# ESP32_UWB.net
KiCad netlist of a schematic drawn in EAGLE
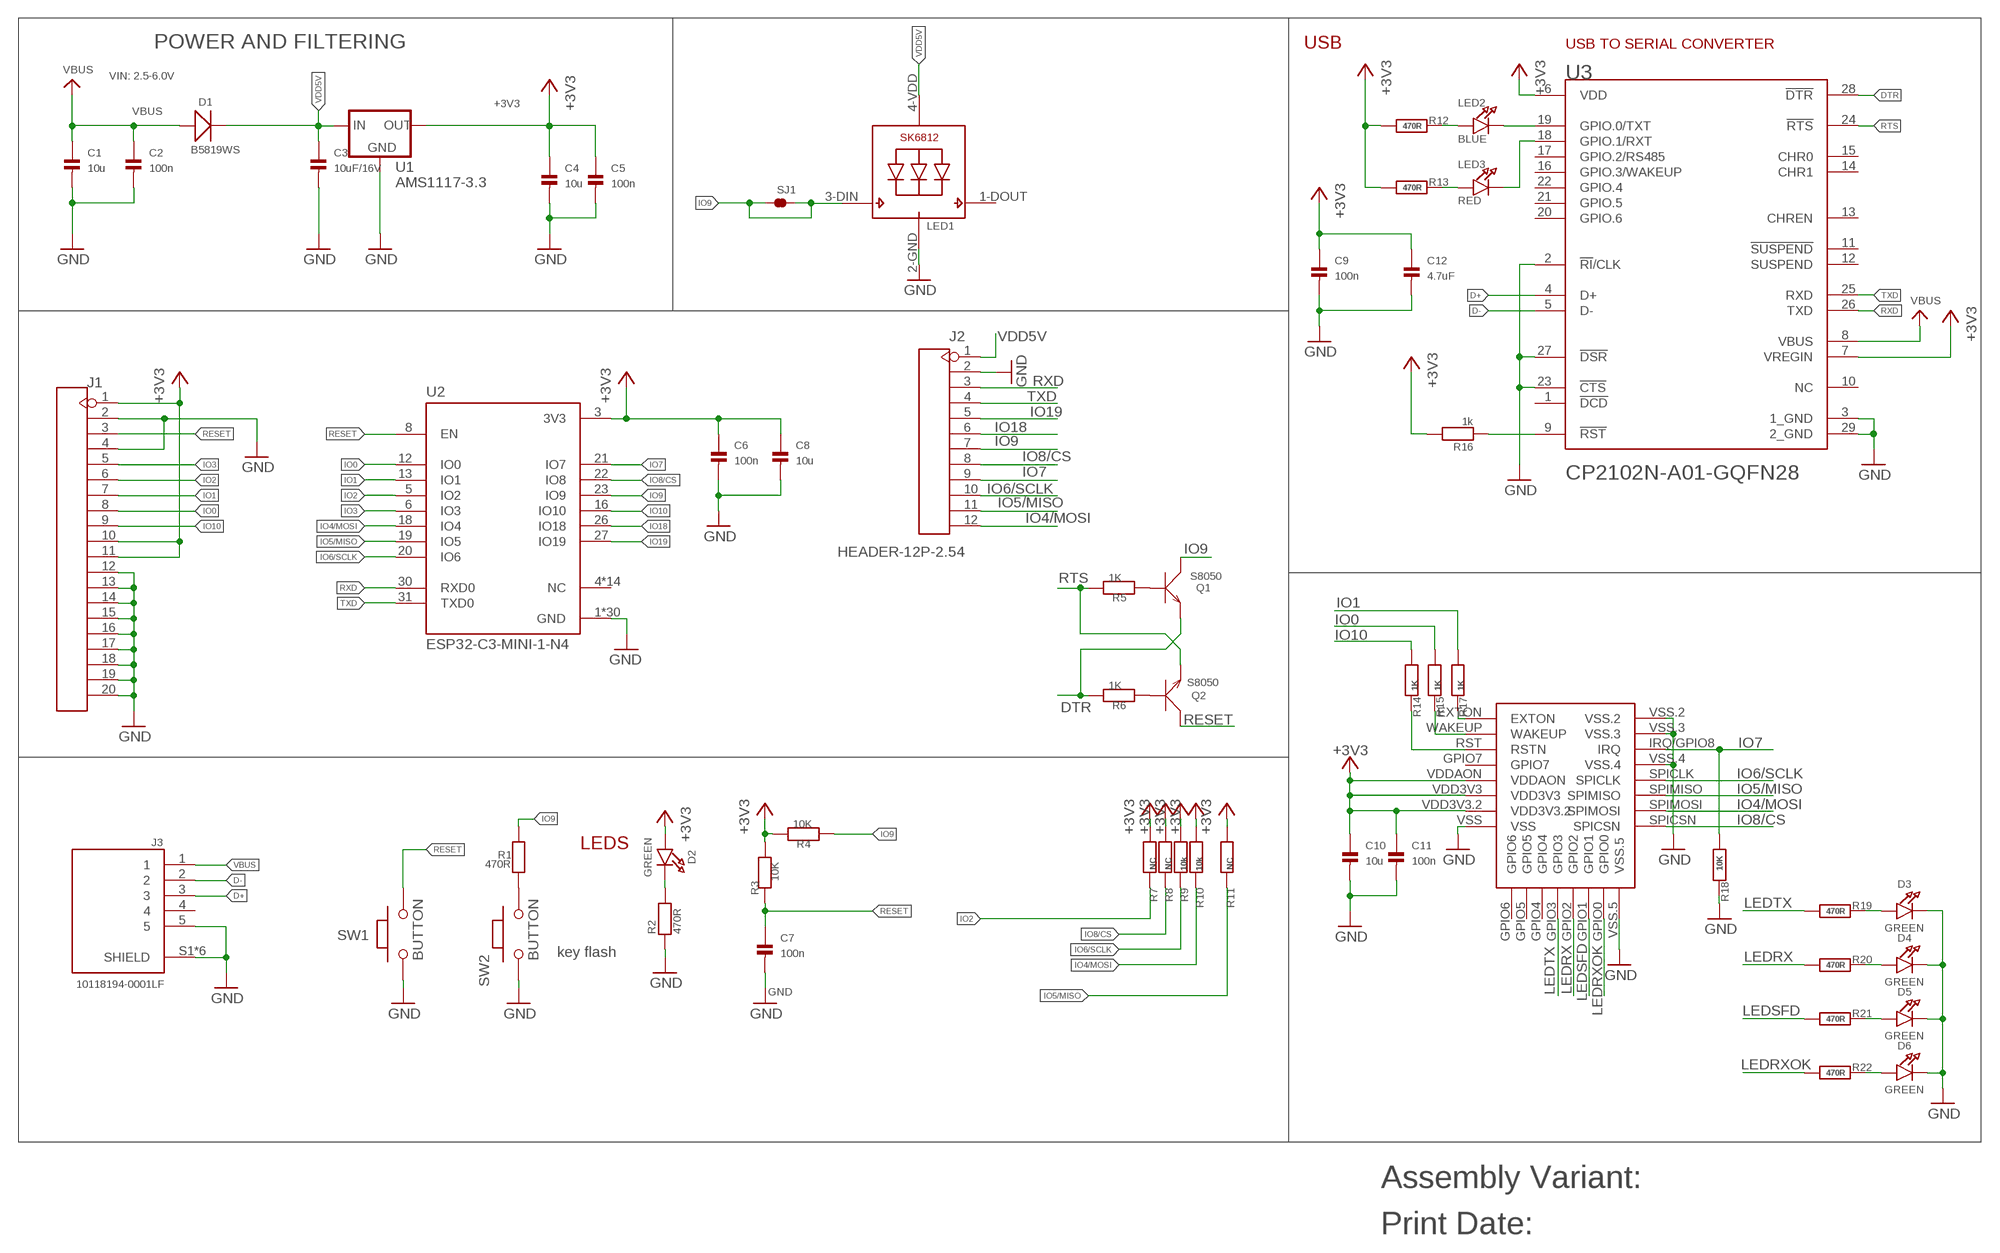
[diagram p0: schematic, sheet 1]

(export (version "E")
  (design (tool "Eeschema 10.0.6"))
  (components
    (comp (ref "C1")
      (value "10u")
      (footprint "eagle-import:0603")
      (libsource (lib "eagle-import") (part "CAP_CERAMIC0603"))
    )
    (comp (ref "C2")
      (value "100n")
      (footprint "eagle-import:0603")
      (libsource (lib "eagle-import") (part "CAP_CERAMIC0603"))
    )
    (comp (ref "C3")
      (value "10uF/16V")
      (footprint "eagle-import:0603")
      (libsource (lib "eagle-import") (part "CAP_CERAMIC0603"))
    )
    (comp (ref "C4")
      (value "10u")
      (footprint "eagle-import:0603")
      (libsource (lib "eagle-import") (part "CAP_CERAMIC0603"))
    )
    (comp (ref "C5")
      (value "100n")
      (footprint "eagle-import:0603")
      (libsource (lib "eagle-import") (part "CAP_CERAMIC0603"))
    )
    (comp (ref "C6")
      (value "100n")
      (footprint "eagle-import:0603")
      (libsource (lib "eagle-import") (part "CAP_CERAMIC0603"))
    )
    (comp (ref "C7")
      (value "100n")
      (footprint "eagle-import:0603")
      (libsource (lib "eagle-import") (part "CAP_CERAMIC0603"))
    )
    (comp (ref "C8")
      (value "10u")
      (footprint "eagle-import:0603")
      (libsource (lib "eagle-import") (part "CAP_CERAMIC0603"))
    )
    (comp (ref "C9")
      (value "100n")
      (footprint "eagle-import:0603")
      (libsource (lib "eagle-import") (part "CAP_CERAMIC0603"))
    )
    (comp (ref "C10")
      (value "10u")
      (footprint "eagle-import:0603")
      (libsource (lib "eagle-import") (part "CAP_CERAMIC0603"))
    )
    (comp (ref "C11")
      (value "100n")
      (footprint "eagle-import:0603")
      (libsource (lib "eagle-import") (part "CAP_CERAMIC0603"))
    )
    (comp (ref "C12")
      (value "4.7uF")
      (footprint "eagle-import:0603")
      (libsource (lib "eagle-import") (part "CAP_CERAMIC0603"))
    )
    (comp (ref "D1")
      (value "B5819WS")
      (footprint "eagle-import:SOD323")
      (libsource (lib "eagle-import") (part "D'0805'"))
    )
    (comp (ref "D2")
      (value "GREEN")
      (footprint "eagle-import:CHIPLED_0805_NOOUTLINE")
      (libsource (lib "eagle-import") (part "microbuilder_LED0805_NOOUTLINE"))
    )
    (comp (ref "D3")
      (value "GREEN")
      (footprint "eagle-import:CHIPLED_0805_NOOUTLINE")
      (libsource (lib "eagle-import") (part "microbuilder_LED0805_NOOUTLINE"))
    )
    (comp (ref "D4")
      (value "GREEN")
      (footprint "eagle-import:CHIPLED_0805_NOOUTLINE")
      (libsource (lib "eagle-import") (part "microbuilder_LED0805_NOOUTLINE"))
    )
    (comp (ref "D5")
      (value "GREEN")
      (footprint "eagle-import:CHIPLED_0805_NOOUTLINE")
      (libsource (lib "eagle-import") (part "microbuilder_LED0805_NOOUTLINE"))
    )
    (comp (ref "D6")
      (value "GREEN")
      (footprint "eagle-import:CHIPLED_0805_NOOUTLINE")
      (libsource (lib "eagle-import") (part "microbuilder_LED0805_NOOUTLINE"))
    )
    (comp (ref "J1")
      (value "HEADER-20P-2.54")
      (footprint "eagle-import:20P-2.54")
      (libsource (lib "eagle-import") (part "HEADER-20P-2.54"))
    )
    (comp (ref "J2")
      (value "HEADER-12P-2.54")
      (footprint "eagle-import:12P-2.54")
      (libsource (lib "eagle-import") (part "HEADER-12P-2.54"))
    )
    (comp (ref "J3")
      (value "10118194-0001LF")
      (footprint "eagle-import:AMPHENOL_10118194-0001LF")
      (fields (field (name "MF") "Amphenol ICC"))
      (libsource (lib "eagle-import") (part "10118194-0001LF"))
    )
    (comp (ref "LED1")
      (value "SK6812_3535")
      (footprint "eagle-import:LED3535")
      (libsource (lib "eagle-import") (part "SK6812_3535"))
    )
    (comp (ref "LED2")
      (value "BLUE")
      (footprint "eagle-import:CHIPLED_0603_NOOUTLINE")
      (libsource (lib "eagle-import") (part "LED0603_NOOUTLINE"))
    )
    (comp (ref "LED3")
      (value "RED")
      (footprint "eagle-import:CHIPLED_0603_NOOUTLINE")
      (libsource (lib "eagle-import") (part "LED0603_NOOUTLINE"))
    )
    (comp (ref "Q1")
      (value "S8050")
      (footprint "eagle-import:SOT23")
      (libsource (lib "eagle-import") (part "TRANSISTOR-NPN-SOT23"))
    )
    (comp (ref "Q2")
      (value "S8050")
      (footprint "eagle-import:SOT23")
      (libsource (lib "eagle-import") (part "TRANSISTOR-NPN-SOT23"))
    )
    (comp (ref "R1")
      (value "470R")
      (footprint "eagle-import:0603")
      (libsource (lib "eagle-import") (part "RESISTOR0603"))
    )
    (comp (ref "R2")
      (value "470R")
      (footprint "eagle-import:0603")
      (libsource (lib "eagle-import") (part "RESISTOR0603"))
    )
    (comp (ref "R3")
      (value "10K")
      (footprint "eagle-import:0603")
      (libsource (lib "eagle-import") (part "RESISTOR0603"))
    )
    (comp (ref "R4")
      (value "10K")
      (footprint "eagle-import:0603")
      (libsource (lib "eagle-import") (part "RESISTOR0603"))
    )
    (comp (ref "R5")
      (value "1K")
      (footprint "eagle-import:0603")
      (libsource (lib "eagle-import") (part "RESISTOR0603"))
    )
    (comp (ref "R6")
      (value "1K")
      (footprint "eagle-import:0603")
      (libsource (lib "eagle-import") (part "RESISTOR0603"))
    )
    (comp (ref "R7")
      (value "NC")
      (footprint "eagle-import:0603")
      (libsource (lib "eagle-import") (part "RESISTOR0603"))
    )
    (comp (ref "R8")
      (value "NC")
      (footprint "eagle-import:0603")
      (libsource (lib "eagle-import") (part "RESISTOR0603"))
    )
    (comp (ref "R9")
      (value "10k")
      (footprint "eagle-import:0603")
      (libsource (lib "eagle-import") (part "RESISTOR0603"))
    )
    (comp (ref "R10")
      (value "10k")
      (footprint "eagle-import:0603")
      (libsource (lib "eagle-import") (part "RESISTOR0603"))
    )
    (comp (ref "R11")
      (value "NC")
      (footprint "eagle-import:0603")
      (libsource (lib "eagle-import") (part "RESISTOR0603"))
    )
    (comp (ref "R12")
      (value "470R")
      (footprint "eagle-import:0603")
      (libsource (lib "eagle-import") (part "RESISTOR0603"))
    )
    (comp (ref "R13")
      (value "470R")
      (footprint "eagle-import:0603")
      (libsource (lib "eagle-import") (part "RESISTOR0603"))
    )
    (comp (ref "R14")
      (value "1K")
      (footprint "eagle-import:0603")
      (libsource (lib "eagle-import") (part "RESISTOR0603"))
    )
    (comp (ref "R15")
      (value "1K")
      (footprint "eagle-import:0603")
      (libsource (lib "eagle-import") (part "RESISTOR0603"))
    )
    (comp (ref "R16")
      (value "1k")
      (footprint "eagle-import:0603")
      (libsource (lib "eagle-import") (part "RESISTOR0603"))
    )
    (comp (ref "R17")
      (value "1K")
      (footprint "eagle-import:0603")
      (libsource (lib "eagle-import") (part "RESISTOR0603"))
    )
    (comp (ref "R18")
      (value "10K")
      (footprint "eagle-import:0603")
      (libsource (lib "eagle-import") (part "RESISTOR0603"))
    )
    (comp (ref "R19")
      (value "470R")
      (footprint "eagle-import:0603")
      (libsource (lib "eagle-import") (part "RESISTOR0603"))
    )
    (comp (ref "R20")
      (value "470R")
      (footprint "eagle-import:0603")
      (libsource (lib "eagle-import") (part "RESISTOR0603"))
    )
    (comp (ref "R21")
      (value "470R")
      (footprint "eagle-import:0603")
      (libsource (lib "eagle-import") (part "RESISTOR0603"))
    )
    (comp (ref "R22")
      (value "470R")
      (footprint "eagle-import:0603")
      (libsource (lib "eagle-import") (part "RESISTOR0603"))
    )
    (comp (ref "SJ1")
      (value "SJS")
      (footprint "eagle-import:SJ_S")
      (libsource (lib "eagle-import") (part "SJS"))
    )
    (comp (ref "SW1")
      (value "BUTTON")
      (footprint "eagle-import:157SW")
      (libsource (lib "eagle-import") (part "PB157"))
    )
    (comp (ref "SW2")
      (value "BUTTON")
      (footprint "eagle-import:157SW")
      (libsource (lib "eagle-import") (part "PB157"))
    )
    (comp (ref "U1")
      (value "AMS1117-3.3")
      (footprint "eagle-import:SOT223")
      (libsource (lib "eagle-import") (part "V_REG_MIC2920"))
    )
    (comp (ref "U2")
      (value "ESP32-C3-MINI-1-N4")
      (footprint "eagle-import:XCVR_ESP32-C3-MINI-1-N4")
      (fields (field (name "MF") "Espressif Systems"))
      (libsource (lib "eagle-import") (part "ESP32-C3-MINI-1-N4"))
    )
    (comp (ref "U3")
      (value "SILICON_LABS_CP2102N-A01-GQFN28SILICON_LABS_CP2102N-A01-GQFN28_0_3")
      (footprint "eagle-import:SILICON_LABS_CP2102N-A01-GQFN28_3")
      (fields
        (field (name "DIGIKEY_PART_NUMBER") "336-3694-ND")
        (field (name "MF") "Silicon Labs")
        (field (name "MOUSER_PART_NUMBER") "634-CP2102NA01GQFN28")
      )
      (libsource (lib "eagle-import") (part "SILICON_LABS_CP2102N-A01-GQFN28SILICON_LABS_CP2102N-A01-GQFN28_0_3"))
    )
    (comp (ref "U4")
      (value "DWM1000")
      (footprint "eagle-import:DWM1000")
      (libsource (lib "eagle-import") (part "DWM1000"))
    )
  )
  (nets
    (net (code "1") (name "+3V3") (class "Default")
      (node (ref "C10") (pin "1") (pinfunction "1_1") (pintype "passive"))
      (node (ref "C11") (pin "1") (pinfunction "1_1") (pintype "passive"))
      (node (ref "C12") (pin "1") (pinfunction "1_1") (pintype "passive"))
      (node (ref "C4") (pin "1") (pinfunction "1_1") (pintype "passive"))
      (node (ref "C5") (pin "1") (pinfunction "1_1") (pintype "passive"))
      (node (ref "C6") (pin "1") (pinfunction "1_1") (pintype "passive"))
      (node (ref "C8") (pin "1") (pinfunction "1_1") (pintype "passive"))
      (node (ref "C9") (pin "1") (pinfunction "1_1") (pintype "passive"))
      (node (ref "D2") (pin "A") (pinfunction "A_A") (pintype "passive"))
      (node (ref "J1") (pin "1") (pinfunction "P$1_1") (pintype "bidirectional"))
      (node (ref "J1") (pin "10") (pinfunction "P$10_10") (pintype "bidirectional"))
      (node (ref "J1") (pin "11") (pinfunction "P$11_11") (pintype "bidirectional"))
      (node (ref "R10") (pin "1") (pinfunction "1_1") (pintype "passive"))
      (node (ref "R11") (pin "1") (pinfunction "1_1") (pintype "passive"))
      (node (ref "R12") (pin "1") (pinfunction "1_1") (pintype "passive"))
      (node (ref "R13") (pin "1") (pinfunction "1_1") (pintype "passive"))
      (node (ref "R16") (pin "2") (pinfunction "2_2") (pintype "passive"))
      (node (ref "R3") (pin "2") (pinfunction "2_2") (pintype "passive"))
      (node (ref "R4") (pin "2") (pinfunction "2_2") (pintype "passive"))
      (node (ref "R7") (pin "1") (pinfunction "1_1") (pintype "passive"))
      (node (ref "R8") (pin "1") (pinfunction "1_1") (pintype "passive"))
      (node (ref "R9") (pin "1") (pinfunction "1_1") (pintype "passive"))
      (node (ref "U1") (pin "3") (pinfunction "OUT_3") (pintype "passive"))
      (node (ref "U2") (pin "3") (pinfunction "3V3_3") (pintype "power_in"))
      (node (ref "U3") (pin "6") (pinfunction "VDD_6") (pintype "power_in"))
      (node (ref "U3") (pin "7") (pinfunction "VREGIN_7") (pintype "input"))
      (node (ref "U4") (pin "VDD3V3") (pinfunction "VDD3V3_VDD3V3") (pintype "bidirectional"))
      (node (ref "U4") (pin "VDD3V3.2") (pinfunction "VDD3V3.2_VDD3V3.2") (pintype "bidirectional"))
      (node (ref "U4") (pin "VDDAON") (pinfunction "VDDAON_VDDAON") (pintype "bidirectional"))
    )
    (net (code "2") (name "/LEDRX") (class "Default")
      (node (ref "R20") (pin "1") (pinfunction "1_1") (pintype "passive"))
      (node (ref "U4") (pin "GPIO2") (pinfunction "GPIO2_GPIO2") (pintype "bidirectional"))
    )
    (net (code "3") (name "/LEDRXOK") (class "Default")
      (node (ref "R22") (pin "1") (pinfunction "1_1") (pintype "passive"))
      (node (ref "U4") (pin "GPIO0") (pinfunction "GPIO0_GPIO0") (pintype "bidirectional"))
    )
    (net (code "4") (name "/LEDSFD") (class "Default")
      (node (ref "R21") (pin "1") (pinfunction "1_1") (pintype "passive"))
      (node (ref "U4") (pin "GPIO1") (pinfunction "GPIO1_GPIO1") (pintype "bidirectional"))
    )
    (net (code "5") (name "/LEDTX") (class "Default")
      (node (ref "R19") (pin "1") (pinfunction "1_1") (pintype "passive"))
      (node (ref "U4") (pin "GPIO3") (pinfunction "GPIO3_GPIO3") (pintype "bidirectional"))
    )
    (net (code "6") (name "D+") (class "Default")
      (node (ref "J3") (pin "3") (pinfunction "3_3") (pintype "passive"))
      (node (ref "U3") (pin "4") (pinfunction "D+_4") (pintype "passive"))
    )
    (net (code "7") (name "D-") (class "Default")
      (node (ref "J3") (pin "2") (pinfunction "2_2") (pintype "passive"))
      (node (ref "U3") (pin "5") (pinfunction "D-_5") (pintype "passive"))
    )
    (net (code "8") (name "DTR") (class "Default")
      (node (ref "Q1") (pin "2") (pinfunction "E_2") (pintype "passive"))
      (node (ref "R6") (pin "2") (pinfunction "2_2") (pintype "passive"))
      (node (ref "U3") (pin "28") (pinfunction "~{DTR}_28") (pintype "output"))
    )
    (net (code "9") (name "GND") (class "Default")
      (node (ref "C1") (pin "2") (pinfunction "2_2") (pintype "passive"))
      (node (ref "C10") (pin "2") (pinfunction "2_2") (pintype "passive"))
      (node (ref "C11") (pin "2") (pinfunction "2_2") (pintype "passive"))
      (node (ref "C12") (pin "2") (pinfunction "2_2") (pintype "passive"))
      (node (ref "C2") (pin "2") (pinfunction "2_2") (pintype "passive"))
      (node (ref "C3") (pin "2") (pinfunction "2_2") (pintype "passive"))
      (node (ref "C4") (pin "2") (pinfunction "2_2") (pintype "passive"))
      (node (ref "C5") (pin "2") (pinfunction "2_2") (pintype "passive"))
      (node (ref "C6") (pin "2") (pinfunction "2_2") (pintype "passive"))
      (node (ref "C7") (pin "2") (pinfunction "2_2") (pintype "passive"))
      (node (ref "C8") (pin "2") (pinfunction "2_2") (pintype "passive"))
      (node (ref "C9") (pin "2") (pinfunction "2_2") (pintype "passive"))
      (node (ref "D3") (pin "C") (pinfunction "C_C") (pintype "passive"))
      (node (ref "D4") (pin "C") (pinfunction "C_C") (pintype "passive"))
      (node (ref "D5") (pin "C") (pinfunction "C_C") (pintype "passive"))
      (node (ref "D6") (pin "C") (pinfunction "C_C") (pintype "passive"))
      (node (ref "J1") (pin "12") (pinfunction "P$12_12") (pintype "bidirectional"))
      (node (ref "J1") (pin "13") (pinfunction "P$13_13") (pintype "bidirectional"))
      (node (ref "J1") (pin "14") (pinfunction "P$14_14") (pintype "bidirectional"))
      (node (ref "J1") (pin "15") (pinfunction "P$15_15") (pintype "bidirectional"))
      (node (ref "J1") (pin "16") (pinfunction "P$16_16") (pintype "bidirectional"))
      (node (ref "J1") (pin "17") (pinfunction "P$17_17") (pintype "bidirectional"))
      (node (ref "J1") (pin "18") (pinfunction "P$18_18") (pintype "bidirectional"))
      (node (ref "J1") (pin "19") (pinfunction "P$19_19") (pintype "bidirectional"))
      (node (ref "J1") (pin "2") (pinfunction "P$2_2") (pintype "bidirectional"))
      (node (ref "J1") (pin "20") (pinfunction "P$20_20") (pintype "bidirectional"))
      (node (ref "J1") (pin "4") (pinfunction "P$4_4") (pintype "bidirectional"))
      (node (ref "J2") (pin "2") (pinfunction "2_2") (pintype "bidirectional"))
      (node (ref "J3") (pin "5") (pinfunction "5_5") (pintype "passive"))
      (node (ref "J3") (pin "S1") (pinfunction "SHIELD_S1") (pintype "passive"))
      (node (ref "J3") (pin "S2") (pinfunction "SHIELD_S2") (pintype "passive"))
      (node (ref "J3") (pin "S3") (pinfunction "SHIELD_S3") (pintype "passive"))
      (node (ref "J3") (pin "S4") (pinfunction "SHIELD_S4") (pintype "passive"))
      (node (ref "J3") (pin "S5") (pinfunction "SHIELD_S5") (pintype "passive"))
      (node (ref "J3") (pin "S6") (pinfunction "SHIELD_S6") (pintype "passive"))
      (node (ref "LED1") (pin "2-GND") (pinfunction "GND_2-GND") (pintype "power_in"))
      (node (ref "R18") (pin "2") (pinfunction "2_2") (pintype "passive"))
      (node (ref "R2") (pin "1") (pinfunction "1_1") (pintype "passive"))
      (node (ref "SW1") (pin "1") (pinfunction "1_1") (pintype "passive"))
      (node (ref "SW2") (pin "1") (pinfunction "1_1") (pintype "passive"))
      (node (ref "U1") (pin "2") (pinfunction "GND_2") (pintype "input"))
      (node (ref "U2") (pin "1") (pinfunction "GND_1") (pintype "power_in"))
      (node (ref "U2") (pin "11") (pinfunction "GND_11") (pintype "power_in"))
      (node (ref "U2") (pin "14") (pinfunction "GND_14") (pintype "power_in"))
      (node (ref "U2") (pin "2") (pinfunction "GND_2") (pintype "power_in"))
      (node (ref "U2") (pin "36") (pinfunction "GND_36") (pintype "power_in"))
      (node (ref "U2") (pin "37") (pinfunction "GND_37") (pintype "power_in"))
      (node (ref "U2") (pin "38") (pinfunction "GND_38") (pintype "power_in"))
      (node (ref "U2") (pin "39") (pinfunction "GND_39") (pintype "power_in"))
      (node (ref "U2") (pin "40") (pinfunction "GND_40") (pintype "power_in"))
      (node (ref "U2") (pin "41") (pinfunction "GND_41") (pintype "power_in"))
      (node (ref "U2") (pin "42") (pinfunction "GND_42") (pintype "power_in"))
      (node (ref "U2") (pin "43") (pinfunction "GND_43") (pintype "power_in"))
      (node (ref "U2") (pin "44") (pinfunction "GND_44") (pintype "power_in"))
      (node (ref "U2") (pin "45") (pinfunction "GND_45") (pintype "power_in"))
      (node (ref "U2") (pin "46") (pinfunction "GND_46") (pintype "power_in"))
      (node (ref "U2") (pin "47") (pinfunction "GND_47") (pintype "power_in"))
      (node (ref "U2") (pin "48") (pinfunction "GND_48") (pintype "power_in"))
      (node (ref "U2") (pin "49_1") (pinfunction "GND_49_1") (pintype "power_in"))
      (node (ref "U2") (pin "49_2") (pinfunction "GND_49_2") (pintype "power_in"))
      (node (ref "U2") (pin "49_3") (pinfunction "GND_49_3") (pintype "power_in"))
      (node (ref "U2") (pin "49_4") (pinfunction "GND_49_4") (pintype "power_in"))
      (node (ref "U2") (pin "49_5") (pinfunction "GND_49_5") (pintype "power_in"))
      (node (ref "U2") (pin "49_6") (pinfunction "GND_49_6") (pintype "power_in"))
      (node (ref "U2") (pin "49_7") (pinfunction "GND_49_7") (pintype "power_in"))
      (node (ref "U2") (pin "49_8") (pinfunction "GND_49_8") (pintype "power_in"))
      (node (ref "U2") (pin "49_9") (pinfunction "GND_49_9") (pintype "power_in"))
      (node (ref "U2") (pin "50") (pinfunction "GND_50") (pintype "power_in"))
      (node (ref "U2") (pin "51") (pinfunction "GND_51") (pintype "power_in"))
      (node (ref "U2") (pin "52") (pinfunction "GND_52") (pintype "power_in"))
      (node (ref "U2") (pin "53") (pinfunction "GND_53") (pintype "power_in"))
      (node (ref "U3") (pin "2") (pinfunction "~{RI}/CLK_2") (pintype "input"))
      (node (ref "U3") (pin "23") (pinfunction "~{CTS}_23") (pintype "input"))
      (node (ref "U3") (pin "27") (pinfunction "~{DSR}_27") (pintype "input"))
      (node (ref "U3") (pin "29") (pinfunction "2_GND_29") (pintype "power_in"))
      (node (ref "U3") (pin "3") (pinfunction "1_GND_3") (pintype "power_in"))
      (node (ref "U4") (pin "VSS") (pinfunction "VSS_VSS") (pintype "bidirectional"))
      (node (ref "U4") (pin "VSS.2") (pinfunction "VSS.2_VSS.2") (pintype "bidirectional"))
      (node (ref "U4") (pin "VSS.3") (pinfunction "VSS.3_VSS.3") (pintype "bidirectional"))
      (node (ref "U4") (pin "VSS.4") (pinfunction "VSS.4_VSS.4") (pintype "bidirectional"))
      (node (ref "U4") (pin "VSS.5") (pinfunction "VSS.5_VSS.5") (pintype "bidirectional"))
    )
    (net (code "10") (name "IO0") (class "Default")
      (node (ref "J1") (pin "8") (pinfunction "P$8_8") (pintype "bidirectional"))
      (node (ref "R15") (pin "1") (pinfunction "1_1") (pintype "passive"))
      (node (ref "U2") (pin "12") (pinfunction "IO0_12") (pintype "bidirectional"))
    )
    (net (code "11") (name "IO1") (class "Default")
      (node (ref "J1") (pin "7") (pinfunction "P$7_7") (pintype "bidirectional"))
      (node (ref "R17") (pin "1") (pinfunction "1_1") (pintype "passive"))
      (node (ref "U2") (pin "13") (pinfunction "IO1_13") (pintype "bidirectional"))
    )
    (net (code "12") (name "IO2") (class "Default")
      (node (ref "J1") (pin "6") (pinfunction "P$6_6") (pintype "bidirectional"))
      (node (ref "R7") (pin "2") (pinfunction "2_2") (pintype "passive"))
      (node (ref "U2") (pin "5") (pinfunction "IO2_5") (pintype "bidirectional"))
    )
    (net (code "13") (name "IO3") (class "Default")
      (node (ref "J1") (pin "5") (pinfunction "P$5_5") (pintype "bidirectional"))
      (node (ref "U2") (pin "6") (pinfunction "IO3_6") (pintype "bidirectional"))
    )
    (net (code "14") (name "IO4{slash}MOSI") (class "Default")
      (node (ref "J2") (pin "12") (pinfunction "12_12") (pintype "bidirectional"))
      (node (ref "R10") (pin "2") (pinfunction "2_2") (pintype "passive"))
      (node (ref "U2") (pin "18") (pinfunction "IO4_18") (pintype "bidirectional"))
      (node (ref "U4") (pin "SPIMOSI") (pinfunction "SPIMOSI_SPIMOSI") (pintype "bidirectional"))
    )
    (net (code "15") (name "IO5{slash}MISO") (class "Default")
      (node (ref "J2") (pin "11") (pinfunction "11_11") (pintype "bidirectional"))
      (node (ref "R11") (pin "2") (pinfunction "2_2") (pintype "passive"))
      (node (ref "U2") (pin "19") (pinfunction "IO5_19") (pintype "bidirectional"))
      (node (ref "U4") (pin "SPIMISO") (pinfunction "SPIMISO_SPIMISO") (pintype "bidirectional"))
    )
    (net (code "16") (name "IO6{slash}SCLK") (class "Default")
      (node (ref "J2") (pin "10") (pinfunction "10_10") (pintype "bidirectional"))
      (node (ref "R9") (pin "2") (pinfunction "2_2") (pintype "passive"))
      (node (ref "U2") (pin "20") (pinfunction "IO6_20") (pintype "bidirectional"))
      (node (ref "U4") (pin "SPICLK") (pinfunction "SPICLK_SPICLK") (pintype "bidirectional"))
    )
    (net (code "17") (name "IO7") (class "Default")
      (node (ref "J2") (pin "9") (pinfunction "9_9") (pintype "bidirectional"))
      (node (ref "R18") (pin "1") (pinfunction "1_1") (pintype "passive"))
      (node (ref "U2") (pin "21") (pinfunction "IO7_21") (pintype "bidirectional"))
      (node (ref "U4") (pin "IRQ/GPIO8") (pinfunction "IRQ_IRQ/GPIO8") (pintype "bidirectional"))
    )
    (net (code "18") (name "IO8{slash}CS") (class "Default")
      (node (ref "J2") (pin "8") (pinfunction "8_8") (pintype "bidirectional"))
      (node (ref "R8") (pin "2") (pinfunction "2_2") (pintype "passive"))
      (node (ref "U2") (pin "22") (pinfunction "IO8_22") (pintype "bidirectional"))
      (node (ref "U4") (pin "SPICSN") (pinfunction "SPICSN_SPICSN") (pintype "bidirectional"))
    )
    (net (code "19") (name "IO9") (class "Default")
      (node (ref "J2") (pin "7") (pinfunction "7_7") (pintype "bidirectional"))
      (node (ref "LED1") (pin "3-DIN") (pinfunction "DI_3-DIN") (pintype "input"))
      (node (ref "Q1") (pin "3") (pinfunction "C_3") (pintype "passive"))
      (node (ref "R1") (pin "2") (pinfunction "2_2") (pintype "passive"))
      (node (ref "R4") (pin "1") (pinfunction "1_1") (pintype "passive"))
      (node (ref "SJ1") (pin "1") (pinfunction "1_1") (pintype "passive"))
      (node (ref "SJ1") (pin "2") (pinfunction "2_2") (pintype "passive"))
      (node (ref "U2") (pin "23") (pinfunction "IO9_23") (pintype "bidirectional"))
    )
    (net (code "20") (name "IO10") (class "Default")
      (node (ref "J1") (pin "9") (pinfunction "P$9_9") (pintype "bidirectional"))
      (node (ref "R14") (pin "1") (pinfunction "1_1") (pintype "passive"))
      (node (ref "U2") (pin "16") (pinfunction "IO10_16") (pintype "bidirectional"))
    )
    (net (code "21") (name "IO18") (class "Default")
      (node (ref "J2") (pin "6") (pinfunction "6_6") (pintype "bidirectional"))
      (node (ref "U2") (pin "26") (pinfunction "IO18_26") (pintype "bidirectional"))
    )
    (net (code "22") (name "IO19") (class "Default")
      (node (ref "J2") (pin "5") (pinfunction "5_5") (pintype "bidirectional"))
      (node (ref "U2") (pin "27") (pinfunction "IO19_27") (pintype "bidirectional"))
    )
    (net (code "23") (name "Net-(D2-PadC)") (class "Default")
      (node (ref "D2") (pin "C") (pinfunction "C_C") (pintype "passive"))
      (node (ref "R2") (pin "2") (pinfunction "2_2") (pintype "passive"))
    )
    (net (code "24") (name "Net-(D3-PadA)") (class "Default")
      (node (ref "D3") (pin "A") (pinfunction "A_A") (pintype "passive"))
      (node (ref "R19") (pin "2") (pinfunction "2_2") (pintype "passive"))
    )
    (net (code "25") (name "Net-(D4-PadA)") (class "Default")
      (node (ref "D4") (pin "A") (pinfunction "A_A") (pintype "passive"))
      (node (ref "R20") (pin "2") (pinfunction "2_2") (pintype "passive"))
    )
    (net (code "26") (name "Net-(D5-PadA)") (class "Default")
      (node (ref "D5") (pin "A") (pinfunction "A_A") (pintype "passive"))
      (node (ref "R21") (pin "2") (pinfunction "2_2") (pintype "passive"))
    )
    (net (code "27") (name "Net-(D6-PadA)") (class "Default")
      (node (ref "D6") (pin "A") (pinfunction "A_A") (pintype "passive"))
      (node (ref "R22") (pin "2") (pinfunction "2_2") (pintype "passive"))
    )
    (net (code "28") (name "Net-(LED2-PadA)") (class "Default")
      (node (ref "LED2") (pin "A") (pinfunction "A_A") (pintype "passive"))
      (node (ref "R12") (pin "2") (pinfunction "2_2") (pintype "passive"))
    )
    (net (code "29") (name "Net-(LED3-PadA)") (class "Default")
      (node (ref "LED3") (pin "A") (pinfunction "A_A") (pintype "passive"))
      (node (ref "R13") (pin "2") (pinfunction "2_2") (pintype "passive"))
    )
    (net (code "30") (name "Net-(Q1-B)") (class "Default")
      (node (ref "Q1") (pin "1") (pinfunction "B_1") (pintype "passive"))
      (node (ref "R5") (pin "1") (pinfunction "1_1") (pintype "passive"))
    )
    (net (code "31") (name "Net-(Q2-B)") (class "Default")
      (node (ref "Q2") (pin "1") (pinfunction "B_1") (pintype "passive"))
      (node (ref "R6") (pin "1") (pinfunction "1_1") (pintype "passive"))
    )
    (net (code "32") (name "Net-(R1-Pad1)") (class "Default")
      (node (ref "R1") (pin "1") (pinfunction "1_1") (pintype "passive"))
      (node (ref "SW2") (pin "2") (pinfunction "2_2") (pintype "passive"))
    )
    (net (code "33") (name "Net-(R15-Pad2)") (class "Default")
      (node (ref "R15") (pin "2") (pinfunction "2_2") (pintype "passive"))
      (node (ref "U4") (pin "WAKEUP") (pinfunction "WAKEUP_WAKEUP") (pintype "bidirectional"))
    )
    (net (code "34") (name "Net-(R17-Pad2)") (class "Default")
      (node (ref "R17") (pin "2") (pinfunction "2_2") (pintype "passive"))
      (node (ref "U4") (pin "EXTON") (pinfunction "EXTON_EXTON") (pintype "bidirectional"))
    )
    (net (code "35") (name "Net-(U3-GPIO.0{slash}TXT)") (class "Default")
      (node (ref "LED2") (pin "C") (pinfunction "C_C") (pintype "passive"))
      (node (ref "U3") (pin "19") (pinfunction "GPIO.0/TXT_19") (pintype "bidirectional"))
    )
    (net (code "36") (name "Net-(U3-GPIO.1{slash}RXT)") (class "Default")
      (node (ref "LED3") (pin "C") (pinfunction "C_C") (pintype "passive"))
      (node (ref "U3") (pin "18") (pinfunction "GPIO.1/RXT_18") (pintype "bidirectional"))
    )
    (net (code "37") (name "Net-(U3-~{RST})") (class "Default")
      (node (ref "R16") (pin "1") (pinfunction "1_1") (pintype "passive"))
      (node (ref "U3") (pin "9") (pinfunction "~{RST}_9") (pintype "input"))
    )
    (net (code "38") (name "Net-(U4-RSTN)") (class "Default")
      (node (ref "R14") (pin "2") (pinfunction "2_2") (pintype "passive"))
      (node (ref "U4") (pin "RST") (pinfunction "RSTN_RST") (pintype "bidirectional"))
    )
    (net (code "39") (name "RESET") (class "Default")
      (node (ref "C7") (pin "1") (pinfunction "1_1") (pintype "passive"))
      (node (ref "J1") (pin "3") (pinfunction "P$3_3") (pintype "bidirectional"))
      (node (ref "Q2") (pin "3") (pinfunction "C_3") (pintype "passive"))
      (node (ref "R3") (pin "1") (pinfunction "1_1") (pintype "passive"))
      (node (ref "SW1") (pin "2") (pinfunction "2_2") (pintype "passive"))
      (node (ref "U2") (pin "8") (pinfunction "EN_8") (pintype "input"))
    )
    (net (code "40") (name "RTS") (class "Default")
      (node (ref "Q2") (pin "2") (pinfunction "E_2") (pintype "passive"))
      (node (ref "R5") (pin "2") (pinfunction "2_2") (pintype "passive"))
      (node (ref "U3") (pin "24") (pinfunction "~{RTS}_24") (pintype "output"))
    )
    (net (code "41") (name "RXD") (class "Default")
      (node (ref "J2") (pin "3") (pinfunction "3_3") (pintype "bidirectional"))
      (node (ref "U2") (pin "30") (pinfunction "RXD0_30") (pintype "bidirectional"))
      (node (ref "U3") (pin "26") (pinfunction "TXD_26") (pintype "output"))
    )
    (net (code "42") (name "TXD") (class "Default")
      (node (ref "J2") (pin "4") (pinfunction "4_4") (pintype "bidirectional"))
      (node (ref "U2") (pin "31") (pinfunction "TXD0_31") (pintype "bidirectional"))
      (node (ref "U3") (pin "25") (pinfunction "RXD_25") (pintype "input"))
    )
    (net (code "43") (name "VBUS") (class "Default")
      (node (ref "C1") (pin "1") (pinfunction "1_1") (pintype "passive"))
      (node (ref "C2") (pin "1") (pinfunction "1_1") (pintype "passive"))
      (node (ref "D1") (pin "+") (pinfunction "+_+") (pintype "passive"))
      (node (ref "J3") (pin "1") (pinfunction "1_1") (pintype "passive"))
      (node (ref "U3") (pin "8") (pinfunction "VBUS_8") (pintype "input"))
    )
    (net (code "44") (name "VDD5V") (class "Default")
      (node (ref "C3") (pin "1") (pinfunction "1_1") (pintype "passive"))
      (node (ref "D1") (pin "-") (pinfunction "-_-") (pintype "passive"))
      (node (ref "J2") (pin "1") (pinfunction "1_1") (pintype "bidirectional"))
      (node (ref "LED1") (pin "4-VDD") (pinfunction "VDD_4-VDD") (pintype "power_in"))
      (node (ref "U1") (pin "1") (pinfunction "IN_1") (pintype "input"))
    )
    (net (code "45") (name "unconnected-(J3-Pad4)") (class "Default")
      (node (ref "J3") (pin "4") (pinfunction "4_4") (pintype "passive"))
    )
    (net (code "46") (name "unconnected-(LED1-DO-Pad1-DOUT)") (class "Default")
      (node (ref "LED1") (pin "1-DOUT") (pinfunction "DO_1-DOUT") (pintype "output"))
    )
    (net (code "47") (name "unconnected-(U2-NC-Pad4)") (class "Default")
      (node (ref "U2") (pin "4") (pinfunction "NC_4") (pintype "no_connect"))
    )
    (net (code "48") (name "unconnected-(U2-NC-Pad7)") (class "Default")
      (node (ref "U2") (pin "7") (pinfunction "NC_7") (pintype "no_connect"))
    )
    (net (code "49") (name "unconnected-(U2-NC-Pad9)") (class "Default")
      (node (ref "U2") (pin "9") (pinfunction "NC_9") (pintype "no_connect"))
    )
    (net (code "50") (name "unconnected-(U2-NC-Pad10)") (class "Default")
      (node (ref "U2") (pin "10") (pinfunction "NC_10") (pintype "no_connect"))
    )
    (net (code "51") (name "unconnected-(U2-NC-Pad15)") (class "Default")
      (node (ref "U2") (pin "15") (pinfunction "NC_15") (pintype "no_connect"))
    )
    (net (code "52") (name "unconnected-(U2-NC-Pad17)") (class "Default")
      (node (ref "U2") (pin "17") (pinfunction "NC_17") (pintype "no_connect"))
    )
    (net (code "53") (name "unconnected-(U2-NC-Pad24)") (class "Default")
      (node (ref "U2") (pin "24") (pinfunction "NC_24") (pintype "no_connect"))
    )
    (net (code "54") (name "unconnected-(U2-NC-Pad25)") (class "Default")
      (node (ref "U2") (pin "25") (pinfunction "NC_25") (pintype "no_connect"))
    )
    (net (code "55") (name "unconnected-(U2-NC-Pad28)") (class "Default")
      (node (ref "U2") (pin "28") (pinfunction "NC_28") (pintype "no_connect"))
    )
    (net (code "56") (name "unconnected-(U2-NC-Pad29)") (class "Default")
      (node (ref "U2") (pin "29") (pinfunction "NC_29") (pintype "no_connect"))
    )
    (net (code "57") (name "unconnected-(U2-NC-Pad32)") (class "Default")
      (node (ref "U2") (pin "32") (pinfunction "NC_32") (pintype "no_connect"))
    )
    (net (code "58") (name "unconnected-(U2-NC-Pad33)") (class "Default")
      (node (ref "U2") (pin "33") (pinfunction "NC_33") (pintype "no_connect"))
    )
    (net (code "59") (name "unconnected-(U2-NC-Pad34)") (class "Default")
      (node (ref "U2") (pin "34") (pinfunction "NC_34") (pintype "no_connect"))
    )
    (net (code "60") (name "unconnected-(U2-NC-Pad35)") (class "Default")
      (node (ref "U2") (pin "35") (pinfunction "NC_35") (pintype "no_connect"))
    )
    (net (code "61") (name "unconnected-(U3-CHR0-Pad15)") (class "Default")
      (node (ref "U3") (pin "15") (pinfunction "CHR0_15") (pintype "output"))
    )
    (net (code "62") (name "unconnected-(U3-CHR1-Pad14)") (class "Default")
      (node (ref "U3") (pin "14") (pinfunction "CHR1_14") (pintype "output"))
    )
    (net (code "63") (name "unconnected-(U3-CHREN-Pad13)") (class "Default")
      (node (ref "U3") (pin "13") (pinfunction "CHREN_13") (pintype "output"))
    )
    (net (code "64") (name "unconnected-(U3-GPIO.2{slash}RS485-Pad17)") (class "Default")
      (node (ref "U3") (pin "17") (pinfunction "GPIO.2/RS485_17") (pintype "bidirectional"))
    )
    (net (code "65") (name "unconnected-(U3-GPIO.3{slash}WAKEUP-Pad16)") (class "Default")
      (node (ref "U3") (pin "16") (pinfunction "GPIO.3/WAKEUP_16") (pintype "bidirectional"))
    )
    (net (code "66") (name "unconnected-(U3-GPIO.4-Pad22)") (class "Default")
      (node (ref "U3") (pin "22") (pinfunction "GPIO.4_22") (pintype "bidirectional"))
    )
    (net (code "67") (name "unconnected-(U3-GPIO.5-Pad21)") (class "Default")
      (node (ref "U3") (pin "21") (pinfunction "GPIO.5_21") (pintype "bidirectional"))
    )
    (net (code "68") (name "unconnected-(U3-GPIO.6-Pad20)") (class "Default")
      (node (ref "U3") (pin "20") (pinfunction "GPIO.6_20") (pintype "bidirectional"))
    )
    (net (code "69") (name "unconnected-(U3-NC-Pad10)") (class "Default")
      (node (ref "U3") (pin "10") (pinfunction "NC_10") (pintype "passive"))
    )
    (net (code "70") (name "unconnected-(U3-SUSPEND-Pad12)") (class "Default")
      (node (ref "U3") (pin "12") (pinfunction "SUSPEND_12") (pintype "output"))
    )
    (net (code "71") (name "unconnected-(U3-~{DCD}-Pad1)") (class "Default")
      (node (ref "U3") (pin "1") (pinfunction "~{DCD}_1") (pintype "bidirectional"))
    )
    (net (code "72") (name "unconnected-(U3-~{SUSPEND}-Pad11)") (class "Default")
      (node (ref "U3") (pin "11") (pinfunction "~{SUSPEND}_11") (pintype "output"))
    )
    (net (code "73") (name "unconnected-(U4-PadGPIO4)") (class "Default")
      (node (ref "U4") (pin "GPIO4") (pinfunction "GPIO4_GPIO4") (pintype "bidirectional"))
    )
    (net (code "74") (name "unconnected-(U4-PadGPIO5)") (class "Default")
      (node (ref "U4") (pin "GPIO5") (pinfunction "GPIO5_GPIO5") (pintype "bidirectional"))
    )
    (net (code "75") (name "unconnected-(U4-PadGPIO6)") (class "Default")
      (node (ref "U4") (pin "GPIO6") (pinfunction "GPIO6_GPIO6") (pintype "bidirectional"))
    )
    (net (code "76") (name "unconnected-(U4-PadGPIO7)") (class "Default")
      (node (ref "U4") (pin "GPIO7") (pinfunction "GPIO7_GPIO7") (pintype "bidirectional"))
    )
  )
)
